# mixer.net
KiCad netlist of a schematic drawn in Altium Designer
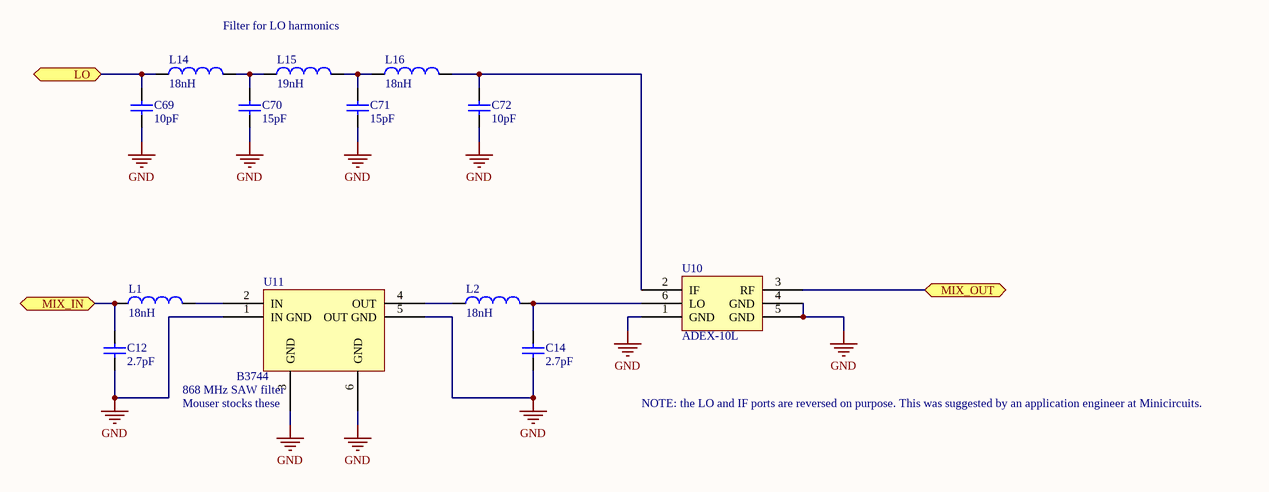
[diagram p0: mixer.SchDoc]

(export (version "E")
  (design (tool "Eeschema 10.0.6"))
  (components
    (comp (ref "C12")
      (value "2.7pF")
      (footprint "0402")
      (description "Capacitor (Semiconductor SIM Model)")
      (fields (field (name "Comment") "Cap Semi") (field (name "PUBLISHER") "Altium Limited"))
      (libsource (lib "Miscellaneous Devices") (part "Cap Semi"))
    )
    (comp (ref "C14")
      (value "2.7pF")
      (footprint "0402")
      (description "Capacitor (Semiconductor SIM Model)")
      (fields (field (name "Comment") "Cap Semi") (field (name "PUBLISHER") "Altium Limited"))
      (libsource (lib "Miscellaneous Devices") (part "Cap Semi"))
    )
    (comp (ref "C69")
      (value "10pF")
      (footprint "0402")
      (description "Capacitor (Semiconductor SIM Model)")
      (fields (field (name "Comment") "Cap Semi") (field (name "PUBLISHER") "Altium Limited"))
      (libsource (lib "Miscellaneous Devices") (part "Cap Semi"))
    )
    (comp (ref "C70")
      (value "15pF")
      (footprint "0402")
      (description "Capacitor (Semiconductor SIM Model)")
      (fields (field (name "Comment") "Cap Semi") (field (name "PUBLISHER") "Altium Limited"))
      (libsource (lib "Miscellaneous Devices") (part "Cap Semi"))
    )
    (comp (ref "C71")
      (value "15pF")
      (footprint "0402")
      (description "Capacitor (Semiconductor SIM Model)")
      (fields (field (name "Comment") "Cap Semi") (field (name "PUBLISHER") "Altium Limited"))
      (libsource (lib "Miscellaneous Devices") (part "Cap Semi"))
    )
    (comp (ref "C72")
      (value "10pF")
      (footprint "0402")
      (description "Capacitor (Semiconductor SIM Model)")
      (fields (field (name "Comment") "Cap Semi") (field (name "PUBLISHER") "Altium Limited"))
      (libsource (lib "Miscellaneous Devices") (part "Cap Semi"))
    )
    (comp (ref "L1")
      (value "18nH")
      (footprint "0402")
      (description "Inductor")
      (fields (field (name "PUBLISHER") "Altium Limited"))
      (libsource (lib "Miscellaneous Devices") (part "Inductor"))
    )
    (comp (ref "L2")
      (value "18nH")
      (footprint "0402")
      (description "Inductor")
      (fields (field (name "PUBLISHER") "Altium Limited"))
      (libsource (lib "Miscellaneous Devices") (part "Inductor"))
    )
    (comp (ref "L14")
      (value "18nH")
      (footprint "0402")
      (description "Inductor")
      (fields (field (name "PUBLISHER") "Altium Limited"))
      (libsource (lib "Miscellaneous Devices") (part "Inductor"))
    )
    (comp (ref "L15")
      (value "19nH")
      (footprint "0402")
      (description "Inductor")
      (fields (field (name "PUBLISHER") "Altium Limited"))
      (libsource (lib "Miscellaneous Devices") (part "Inductor"))
    )
    (comp (ref "L16")
      (value "18nH")
      (footprint "0402")
      (description "Inductor")
      (fields (field (name "PUBLISHER") "Altium Limited"))
      (libsource (lib "Miscellaneous Devices") (part "Inductor"))
    )
    (comp (ref "U10")
      (value "ADEX-10L")
      (description "Passive Mixer")
      (libsource (lib "shield_components") (part "ADEX-10L"))
    )
    (comp (ref "U11") (value "B3744") (libsource (lib "shield_components") (part "B3744")))
  )
  (nets
    (net (code "1") (name "/LO") (class "Default")
      (node (ref "C69") (pin "1") (pinfunction "1_1") (pintype "passive"))
      (node (ref "L14") (pin "1") (pinfunction "1_1") (pintype "passive"))
    )
    (net (code "2") (name "/MIX_IN") (class "Default")
      (node (ref "C12") (pin "2") (pinfunction "2_2") (pintype "passive"))
      (node (ref "L1") (pin "1") (pinfunction "1_1") (pintype "passive"))
    )
    (net (code "3") (name "/MIX_OUT") (class "Default")
      (node (ref "U10") (pin "3") (pinfunction "RF_3") (pintype "passive"))
    )
    (net (code "4") (name "GND") (class "Default")
      (node (ref "C12") (pin "1") (pinfunction "1_1") (pintype "passive"))
      (node (ref "C14") (pin "2") (pinfunction "2_2") (pintype "passive"))
      (node (ref "C69") (pin "2") (pinfunction "2_2") (pintype "passive"))
      (node (ref "C70") (pin "2") (pinfunction "2_2") (pintype "passive"))
      (node (ref "C71") (pin "2") (pinfunction "2_2") (pintype "passive"))
      (node (ref "C72") (pin "2") (pinfunction "2_2") (pintype "passive"))
      (node (ref "U10") (pin "1") (pinfunction "GND_1") (pintype "passive"))
      (node (ref "U10") (pin "4") (pinfunction "GND_4") (pintype "passive"))
      (node (ref "U10") (pin "5") (pinfunction "GND_5") (pintype "passive"))
      (node (ref "U11") (pin "1") (pinfunction "IN_GND_1") (pintype "passive"))
      (node (ref "U11") (pin "3") (pinfunction "GND_3") (pintype "passive"))
      (node (ref "U11") (pin "5") (pinfunction "OUT_GND_5") (pintype "passive"))
      (node (ref "U11") (pin "6") (pinfunction "GND_6") (pintype "passive"))
    )
    (net (code "5") (name "Net-(C70-Pad1)") (class "Default")
      (node (ref "C70") (pin "1") (pinfunction "1_1") (pintype "passive"))
      (node (ref "L14") (pin "2") (pinfunction "2_2") (pintype "passive"))
      (node (ref "L15") (pin "1") (pinfunction "1_1") (pintype "passive"))
    )
    (net (code "6") (name "Net-(C71-Pad1)") (class "Default")
      (node (ref "C71") (pin "1") (pinfunction "1_1") (pintype "passive"))
      (node (ref "L15") (pin "2") (pinfunction "2_2") (pintype "passive"))
      (node (ref "L16") (pin "1") (pinfunction "1_1") (pintype "passive"))
    )
    (net (code "7") (name "Net-(U10-IF)") (class "Default")
      (node (ref "C72") (pin "1") (pinfunction "1_1") (pintype "passive"))
      (node (ref "L16") (pin "2") (pinfunction "2_2") (pintype "passive"))
      (node (ref "U10") (pin "2") (pinfunction "IF_2") (pintype "passive"))
    )
    (net (code "8") (name "Net-(U10-LO)") (class "Default")
      (node (ref "C14") (pin "1") (pinfunction "1_1") (pintype "passive"))
      (node (ref "L2") (pin "2") (pinfunction "2_2") (pintype "passive"))
      (node (ref "U10") (pin "6") (pinfunction "LO_6") (pintype "passive"))
    )
    (net (code "9") (name "Net-(U11-IN)") (class "Default")
      (node (ref "L1") (pin "2") (pinfunction "2_2") (pintype "passive"))
      (node (ref "U11") (pin "2") (pinfunction "IN_2") (pintype "passive"))
    )
    (net (code "10") (name "Net-(U11-OUT)") (class "Default")
      (node (ref "L2") (pin "1") (pinfunction "1_1") (pintype "passive"))
      (node (ref "U11") (pin "4") (pinfunction "OUT_4") (pintype "passive"))
    )
  )
)
